# 4thLPF.net
KiCad netlist of a schematic drawn in EAGLE
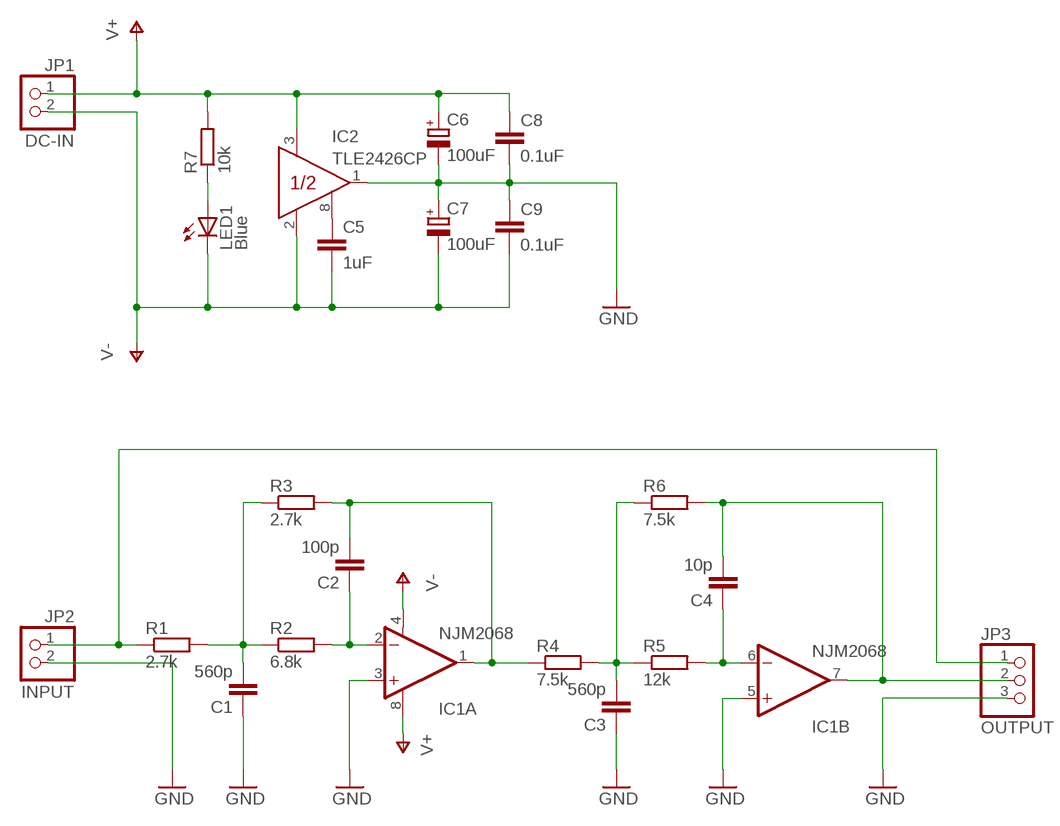
[diagram p0: schematic, sheet 1]

(export (version "E")
  (design (tool "Eeschema 10.0.6"))
  (components
    (comp (ref "C1")
      (value "560p")
      (footprint "eagle-import:C050-035X075")
      (libsource (lib "eagle-import") (part "C-EU050-035X075"))
    )
    (comp (ref "C2")
      (value "100p")
      (footprint "eagle-import:C050-035X075")
      (libsource (lib "eagle-import") (part "C-EU050-035X075"))
    )
    (comp (ref "C3")
      (value "560p")
      (footprint "eagle-import:C050-035X075")
      (libsource (lib "eagle-import") (part "C-EU050-035X075"))
    )
    (comp (ref "C4")
      (value "10p")
      (footprint "eagle-import:C050-024X044")
      (libsource (lib "eagle-import") (part "C-EU050-024X044"))
    )
    (comp (ref "C5")
      (value "1uF")
      (footprint "eagle-import:C050-024X044")
      (libsource (lib "eagle-import") (part "C-EU050-024X044"))
    )
    (comp (ref "C6")
      (value "100uF")
      (footprint "eagle-import:E2,5-6")
      (libsource (lib "eagle-import") (part "CPOL-EUE2.5-6"))
    )
    (comp (ref "C7")
      (value "100uF")
      (footprint "eagle-import:E2,5-6")
      (libsource (lib "eagle-import") (part "CPOL-EUE2.5-6"))
    )
    (comp (ref "C8")
      (value "0.1uF")
      (footprint "eagle-import:C050-024X044")
      (libsource (lib "eagle-import") (part "C-EU050-024X044"))
    )
    (comp (ref "C9")
      (value "0.1uF")
      (footprint "eagle-import:C025-024X044")
      (libsource (lib "eagle-import") (part "C-EU025-024X044"))
    )
    (comp (ref "IC1")
      (value "NJM2068")
      (footprint "eagle-import:DIL08")
      (fields (field (name "MF") "TEXAS INSTRUMENTS") (field (name "MPN") "OPA2134PA"))
      (libsource (lib "eagle-import") (part "OPA2134P"))
    )
    (comp (ref "IC2")
      (value "TLE2426CP")
      (footprint "eagle-import:DIP-8")
      (libsource (lib "eagle-import") (part "TLE2426PC"))
    )
    (comp (ref "JP1")
      (value "DC-IN")
      (footprint "eagle-import:1X02")
      (libsource (lib "eagle-import") (part "PINHD-1X2"))
    )
    (comp (ref "JP2")
      (value "INPUT")
      (footprint "eagle-import:1X02")
      (libsource (lib "eagle-import") (part "PINHD-1X2"))
    )
    (comp (ref "JP3")
      (value "OUTPUT")
      (footprint "eagle-import:1X03")
      (libsource (lib "eagle-import") (part "PINHD-1X3"))
    )
    (comp (ref "LED1")
      (value "Blue")
      (footprint "eagle-import:LED3MM")
      (libsource (lib "eagle-import") (part "LED3MM"))
    )
    (comp (ref "R1")
      (value "2.7k")
      (footprint "eagle-import:0207_7")
      (libsource (lib "eagle-import") (part "R-EU_0207/7"))
    )
    (comp (ref "R2")
      (value "6.8k")
      (footprint "eagle-import:0207_7")
      (libsource (lib "eagle-import") (part "R-EU_0207/7"))
    )
    (comp (ref "R3")
      (value "2.7k")
      (footprint "eagle-import:0207_7")
      (libsource (lib "eagle-import") (part "R-EU_0207/7"))
    )
    (comp (ref "R4")
      (value "7.5k")
      (footprint "eagle-import:0207_7")
      (libsource (lib "eagle-import") (part "R-EU_0207/7"))
    )
    (comp (ref "R5")
      (value "12k")
      (footprint "eagle-import:0207_7")
      (libsource (lib "eagle-import") (part "R-EU_0207/7"))
    )
    (comp (ref "R6")
      (value "7.5k")
      (footprint "eagle-import:0207_7")
      (libsource (lib "eagle-import") (part "R-EU_0207/7"))
    )
    (comp (ref "R7")
      (value "10k")
      (footprint "eagle-import:0207_7")
      (libsource (lib "eagle-import") (part "R-EU_0207/7"))
    )
  )
  (nets
    (net (code "1") (name "GND") (class "Default")
      (node (ref "C1") (pin "1") (pinfunction "1_1") (pintype "passive"))
      (node (ref "C3") (pin "1") (pinfunction "1_1") (pintype "passive"))
      (node (ref "C6") (pin "-") (pinfunction "-_-") (pintype "passive"))
      (node (ref "C7") (pin "+") (pinfunction "+_+") (pintype "passive"))
      (node (ref "C8") (pin "2") (pinfunction "2_2") (pintype "passive"))
      (node (ref "C9") (pin "1") (pinfunction "1_1") (pintype "passive"))
      (node (ref "IC1") (pin "3") (pinfunction "+IN_3") (pintype "input"))
      (node (ref "IC1") (pin "5") (pinfunction "+IN_5") (pintype "input"))
      (node (ref "IC2") (pin "1") (pinfunction "OUT_1") (pintype "passive"))
      (node (ref "JP2") (pin "2") (pinfunction "2_2") (pintype "passive"))
      (node (ref "JP3") (pin "3") (pinfunction "3_3") (pintype "passive"))
    )
    (net (code "2") (name "Net-(C1-Pad2)") (class "Default")
      (node (ref "C1") (pin "2") (pinfunction "2_2") (pintype "passive"))
      (node (ref "R1") (pin "2") (pinfunction "2_2") (pintype "passive"))
      (node (ref "R2") (pin "1") (pinfunction "1_1") (pintype "passive"))
      (node (ref "R3") (pin "1") (pinfunction "1_1") (pintype "passive"))
    )
    (net (code "3") (name "Net-(C3-Pad2)") (class "Default")
      (node (ref "C3") (pin "2") (pinfunction "2_2") (pintype "passive"))
      (node (ref "R4") (pin "2") (pinfunction "2_2") (pintype "passive"))
      (node (ref "R5") (pin "1") (pinfunction "1_1") (pintype "passive"))
      (node (ref "R6") (pin "1") (pinfunction "1_1") (pintype "passive"))
    )
    (net (code "4") (name "Net-(IC1A--IN)") (class "Default")
      (node (ref "C2") (pin "1") (pinfunction "1_1") (pintype "passive"))
      (node (ref "IC1") (pin "2") (pinfunction "-IN_2") (pintype "input"))
      (node (ref "R2") (pin "2") (pinfunction "2_2") (pintype "passive"))
    )
    (net (code "5") (name "Net-(IC1A-OUT)") (class "Default")
      (node (ref "C2") (pin "2") (pinfunction "2_2") (pintype "passive"))
      (node (ref "IC1") (pin "1") (pinfunction "OUT_1") (pintype "output"))
      (node (ref "R3") (pin "2") (pinfunction "2_2") (pintype "passive"))
      (node (ref "R4") (pin "1") (pinfunction "1_1") (pintype "passive"))
    )
    (net (code "6") (name "Net-(IC1B--IN)") (class "Default")
      (node (ref "C4") (pin "1") (pinfunction "1_1") (pintype "passive"))
      (node (ref "IC1") (pin "6") (pinfunction "-IN_6") (pintype "input"))
      (node (ref "R5") (pin "2") (pinfunction "2_2") (pintype "passive"))
    )
    (net (code "7") (name "Net-(IC1B-OUT)") (class "Default")
      (node (ref "C4") (pin "2") (pinfunction "2_2") (pintype "passive"))
      (node (ref "IC1") (pin "7") (pinfunction "OUT_7") (pintype "output"))
      (node (ref "JP3") (pin "2") (pinfunction "2_2") (pintype "passive"))
      (node (ref "R6") (pin "2") (pinfunction "2_2") (pintype "passive"))
    )
    (net (code "8") (name "Net-(IC2-NR)") (class "Default")
      (node (ref "C5") (pin "1") (pinfunction "1_1") (pintype "passive"))
      (node (ref "IC2") (pin "8") (pinfunction "NR_8") (pintype "passive"))
    )
    (net (code "9") (name "Net-(JP2-Pad1)") (class "Default")
      (node (ref "JP2") (pin "1") (pinfunction "1_1") (pintype "passive"))
      (node (ref "JP3") (pin "1") (pinfunction "1_1") (pintype "passive"))
      (node (ref "R1") (pin "1") (pinfunction "1_1") (pintype "passive"))
    )
    (net (code "10") (name "Net-(LED1-PadA)") (class "Default")
      (node (ref "LED1") (pin "A") (pinfunction "A_A") (pintype "passive"))
      (node (ref "R7") (pin "1") (pinfunction "1_1") (pintype "passive"))
    )
    (net (code "11") (name "V+") (class "Default")
      (node (ref "C6") (pin "+") (pinfunction "+_+") (pintype "passive"))
      (node (ref "C8") (pin "1") (pinfunction "1_1") (pintype "passive"))
      (node (ref "IC1") (pin "8") (pinfunction "V+_8") (pintype "power_in"))
      (node (ref "IC2") (pin "3") (pinfunction "IN_3") (pintype "passive"))
      (node (ref "JP1") (pin "1") (pinfunction "1_1") (pintype "passive"))
      (node (ref "R7") (pin "2") (pinfunction "2_2") (pintype "passive"))
    )
    (net (code "12") (name "V-") (class "Default")
      (node (ref "C5") (pin "2") (pinfunction "2_2") (pintype "passive"))
      (node (ref "C7") (pin "-") (pinfunction "-_-") (pintype "passive"))
      (node (ref "C9") (pin "2") (pinfunction "2_2") (pintype "passive"))
      (node (ref "IC1") (pin "4") (pinfunction "V-_4") (pintype "power_in"))
      (node (ref "IC2") (pin "2") (pinfunction "COM_2") (pintype "passive"))
      (node (ref "JP1") (pin "2") (pinfunction "2_2") (pintype "passive"))
      (node (ref "LED1") (pin "K") (pinfunction "C_K") (pintype "passive"))
    )
  )
)
